# ADXL345_5V.net
KiCad netlist of a schematic drawn in Altium Designer
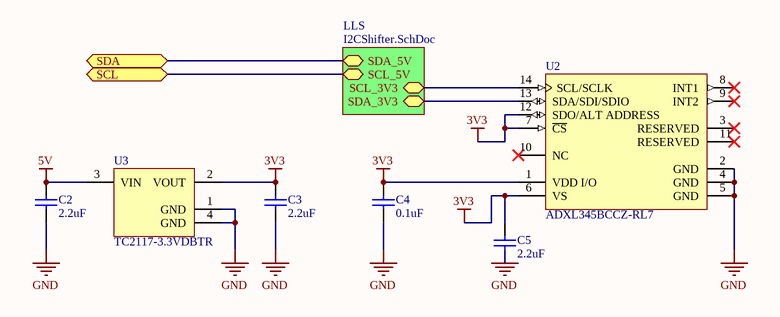
[diagram p0: ADXL345_5V.SchDoc]

(export (version "E")
  (design (tool "Eeschema 10.0.6"))
  (components
    (comp (ref "C2")
      (value "2.2uF")
      (footprint "CAPC0603(1608)100_L")
      (description "CAP 2.2uF 25V ±10% 0603 (1608 Metric) Thickness 1mm SMD")
      (fields (field (name "TOLERANCE") "Â±10%"))
      (libsource (lib "Altium Content Vault") (part "CMP-1035-02767-1"))
    )
    (comp (ref "C3")
      (value "2.2uF")
      (footprint "CAPC0603(1608)100_L")
      (description "CAP 2.2uF 25V ±10% 0603 (1608 Metric) Thickness 1mm SMD")
      (fields (field (name "TOLERANCE") "Â±10%"))
      (libsource (lib "Altium Content Vault") (part "CMP-1035-02767-1"))
    )
    (comp (ref "C4")
      (value "0.1uF")
      (footprint "CAPC0603(1608)100_L")
      (description "CAP 100nF 50V ±5% 0603 (1608 Metric) Thickness 1mm SMD")
      (fields (field (name "TOLERANCE") "Â±5%"))
      (libsource (lib "Altium Content Vault") (part "CMP-1035-02591-1"))
    )
    (comp (ref "C5")
      (value "2.2uF")
      (footprint "CAPC0603(1608)100_L")
      (description "CAP 2.2uF 25V ±10% 0603 (1608 Metric) Thickness 1mm SMD")
      (fields (field (name "TOLERANCE") "Â±10%"))
      (libsource (lib "Altium Content Vault") (part "CMP-1035-02767-1"))
    )
    (comp (ref "U2")
      (value "ADXL345BCCZ-RL7")
      (footprint "ADI-CC-14-1_V")
      (fields (field (name "MANUFACTURER") "Analog Devices"))
      (libsource (lib "Altium Content Vault") (part "ADI-ADXL34X-CC-14-1"))
    )
    (comp (ref "U3")
      (value "TC2117-3.3VDBTR")
      (footprint "SOT-223-DB3_L")
      (description "800 mA Fixed Low Dropout Positive Regulator, 3-Pin SOT-223, Extended Temperature, Tape and Reel")
      (libsource (lib "Altium Content Vault") (part "PM-LINEREG-TC2117-IL4"))
    )
  )
  (nets
    (net (code "2") (name "/SCL_3V3") (class "Default")
      (node (ref "U2") (pin "14") (pinfunction "SCL/SCLK_14") (pintype "input"))
    )
    (net (code "4") (name "/SDA_3V3") (class "Default")
      (node (ref "U2") (pin "13") (pinfunction "SDA/SDI/SDIO_13") (pintype "bidirectional"))
    )
    (net (code "5") (name "3V3") (class "Default")
      (node (ref "C3") (pin "2") (pinfunction "2_2") (pintype "passive"))
      (node (ref "C4") (pin "2") (pinfunction "2_2") (pintype "passive"))
      (node (ref "C5") (pin "2") (pinfunction "2_2") (pintype "passive"))
      (node (ref "U2") (pin "1") (pinfunction "VDD_I/O_1") (pintype "power_in"))
      (node (ref "U2") (pin "12") (pinfunction "SDO/ALT_ADDRESS_12") (pintype "bidirectional"))
      (node (ref "U2") (pin "6") (pinfunction "VS_6") (pintype "power_in"))
      (node (ref "U2") (pin "7") (pinfunction "~{CS}_7") (pintype "input"))
      (node (ref "U3") (pin "2") (pinfunction "VOUT_2") (pintype "power_in"))
    )
    (net (code "6") (name "5V") (class "Default")
      (node (ref "C2") (pin "2") (pinfunction "2_2") (pintype "passive"))
      (node (ref "U3") (pin "3") (pinfunction "VIN_3") (pintype "power_in"))
    )
    (net (code "7") (name "GND") (class "Default")
      (node (ref "C2") (pin "1") (pinfunction "1_1") (pintype "passive"))
      (node (ref "C3") (pin "1") (pinfunction "1_1") (pintype "passive"))
      (node (ref "C4") (pin "1") (pinfunction "1_1") (pintype "passive"))
      (node (ref "C5") (pin "1") (pinfunction "1_1") (pintype "passive"))
      (node (ref "U2") (pin "2") (pinfunction "GND_2") (pintype "power_in"))
      (node (ref "U2") (pin "4") (pinfunction "GND_4") (pintype "power_in"))
      (node (ref "U2") (pin "5") (pinfunction "GND_5") (pintype "power_in"))
      (node (ref "U3") (pin "1") (pinfunction "GND_1") (pintype "power_in"))
      (node (ref "U3") (pin "4") (pinfunction "GND_4") (pintype "power_in"))
    )
    (net (code "8") (name "unconnected-(U2-INT1-Pad8)") (class "Default")
      (node (ref "U2") (pin "8") (pinfunction "INT1_8") (pintype "output+no_connect"))
    )
    (net (code "9") (name "unconnected-(U2-INT2-Pad9)") (class "Default")
      (node (ref "U2") (pin "9") (pinfunction "INT2_9") (pintype "output+no_connect"))
    )
    (net (code "10") (name "unconnected-(U2-NC-Pad10)") (class "Default")
      (node (ref "U2") (pin "10") (pinfunction "NC_10") (pintype "passive+no_connect"))
    )
    (net (code "11") (name "unconnected-(U2-RESERVED-Pad3)") (class "Default")
      (node (ref "U2") (pin "3") (pinfunction "RESERVED_3") (pintype "passive+no_connect"))
    )
    (net (code "12") (name "unconnected-(U2-RESERVED-Pad11)") (class "Default")
      (node (ref "U2") (pin "11") (pinfunction "RESERVED_11") (pintype "passive+no_connect"))
    )
  )
)
